# mask_v_0_0.net
KiCad netlist of a schematic drawn in Altium Designer
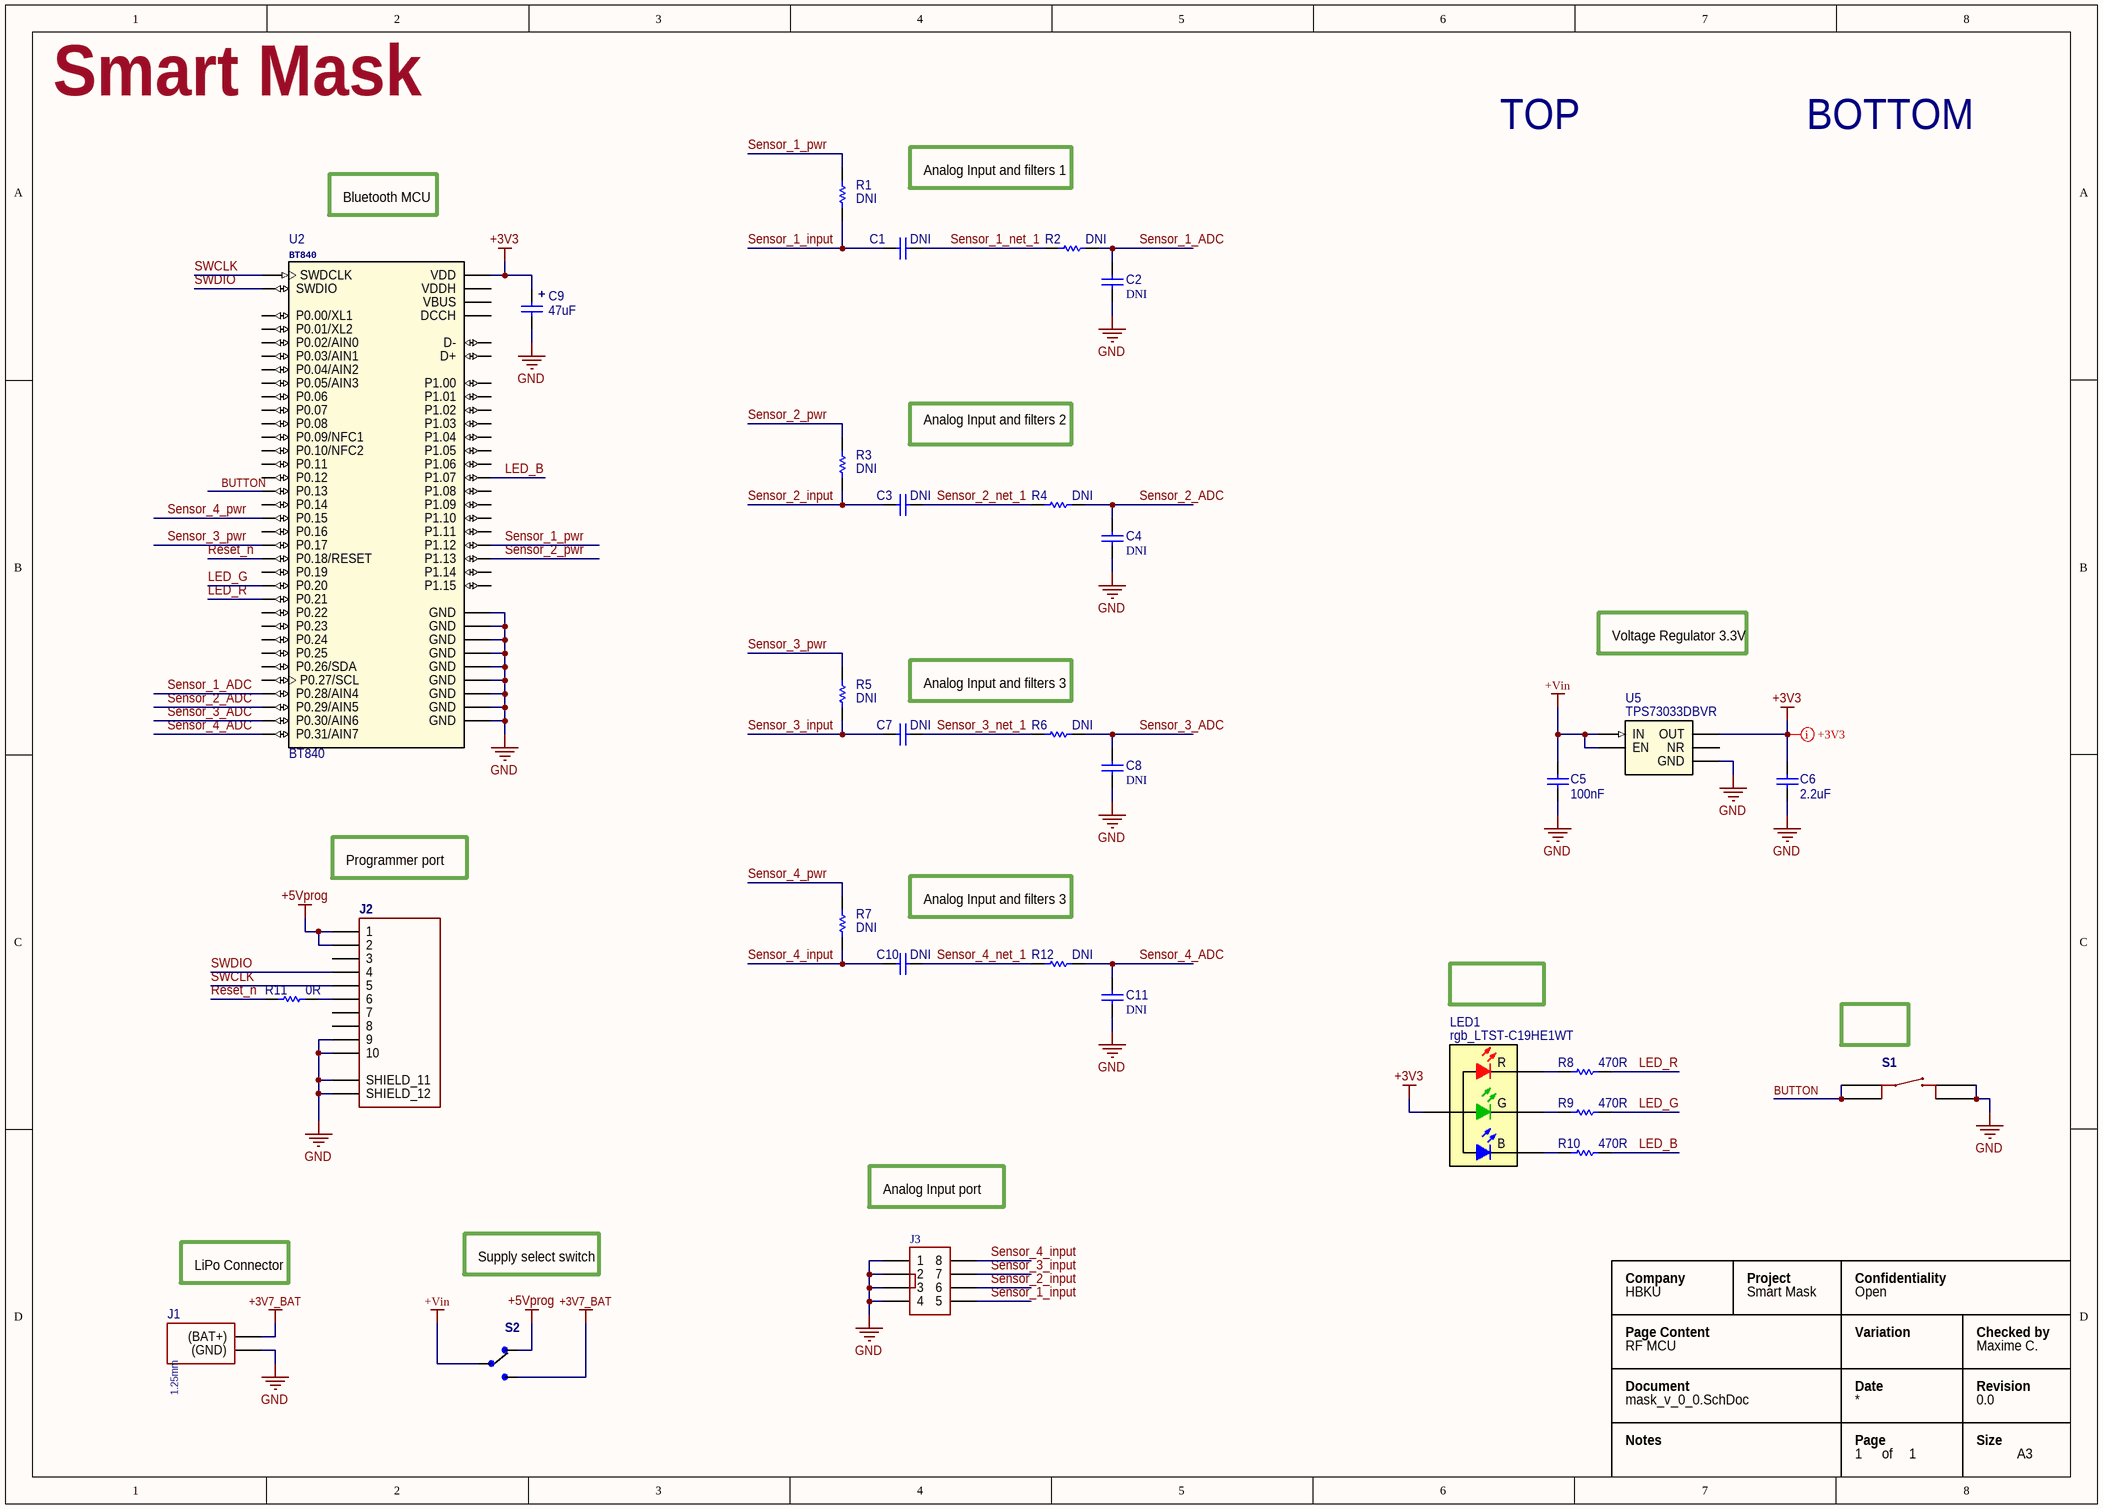
[diagram p0: mask_v_0_0.SchDoc]

(export (version "E")
  (design (tool "Eeschema 10.0.6"))
  (components
    (comp (ref "C1")
      (value "DNI")
      (footprint "C0603_DNI")
      (description "DNI (Do Not Install)")
      (fields (field (name "Comment") "Multilayer Ceramic Capacitor"))
      (libsource (lib "rcl") (part "Cap DNI 0603"))
    )
    (comp (ref "C2")
      (value "DNI")
      (footprint "C0603_DNI")
      (description "DNI (Do Not Install)")
      (fields (field (name "Comment") "Multilayer Ceramic Capacitor"))
      (libsource (lib "rcl") (part "Cap DNI 0603"))
    )
    (comp (ref "C3")
      (value "DNI")
      (footprint "C0603_DNI")
      (description "DNI (Do Not Install)")
      (fields (field (name "Comment") "Multilayer Ceramic Capacitor"))
      (libsource (lib "rcl") (part "Cap DNI 0603"))
    )
    (comp (ref "C4")
      (value "DNI")
      (footprint "C0603_DNI")
      (description "DNI (Do Not Install)")
      (fields (field (name "Comment") "Multilayer Ceramic Capacitor"))
      (libsource (lib "rcl") (part "Cap DNI 0603"))
    )
    (comp (ref "C5")
      (value "100nF")
      (footprint "C0603")
      (description "CAP CER 0.1UF 50V X7R 0603")
      (fields
        (field (name "MANUFACTURER PART NUMBER") "CL10B104KB8NNNL")
        (field (name "MANUFACTURER") "Samsung Electro-Mechanics")
      )
      (libsource (lib "rcl") (part "Cap 100nF 0603 50V"))
    )
    (comp (ref "C6")
      (value "2.2uF")
      (footprint "C0603")
      (description "CAP CER 2.2UF 10V X5R 0603")
      (fields
        (field (name "MANUFACTURER PART NUMBER") "CL10A225KP8NNNC")
        (field (name "MANUFACTURER") "Samsung Electro-Mechanics")
      )
      (libsource (lib "rcl") (part "Cap 2.2uF 0603 50V"))
    )
    (comp (ref "C7")
      (value "DNI")
      (footprint "C0603_DNI")
      (description "DNI (Do Not Install)")
      (fields (field (name "Comment") "Multilayer Ceramic Capacitor"))
      (libsource (lib "rcl") (part "Cap DNI 0603"))
    )
    (comp (ref "C8")
      (value "DNI")
      (footprint "C0603_DNI")
      (description "DNI (Do Not Install)")
      (fields (field (name "Comment") "Multilayer Ceramic Capacitor"))
      (libsource (lib "rcl") (part "Cap DNI 0603"))
    )
    (comp (ref "C9")
      (value "47uF")
      (footprint "C1206")
      (description "CAP TANT 47UF 20% 6.3V 1206")
      (fields
        (field (name "MANUFACTURER PART NUMBER") "F930J476MAA")
        (field (name "MANUFACTURER") "AVX Corporation")
      )
      (libsource (lib "rcl") (part "Cap 47uF 1206 6.3V"))
    )
    (comp (ref "C10")
      (value "DNI")
      (footprint "C0603_DNI")
      (description "DNI (Do Not Install)")
      (fields (field (name "Comment") "Multilayer Ceramic Capacitor"))
      (libsource (lib "rcl") (part "Cap DNI 0603"))
    )
    (comp (ref "C11")
      (value "DNI")
      (footprint "C0603_DNI")
      (description "DNI (Do Not Install)")
      (fields (field (name "Comment") "Multilayer Ceramic Capacitor"))
      (libsource (lib "rcl") (part "Cap DNI 0603"))
    )
    (comp (ref "J1")
      (value "BAT_0530470210")
      (footprint "Bat 1.25 mm")
      (description "CONN HEADER VERT 2POS 1.25MM")
      (fields (field (name "MANUFACTURER") "Molex") (field (name "MANUFACTURER PART NUMBER") "0530470210"))
      (libsource (lib "connectors") (part "BAT_0530470210"))
    )
    (comp (ref "J2")
      (value "FPC-10-pos")
      (footprint "FPC10")
      (description "CONN FFC TOP 10POS 0.50MM R/A \r\nFPC connector SFV10R-2STE1LF  10 positions")
      (fields
        (field (name "MANUFACTURER") "Amphenol ICC (FCI)")
        (field (name "MANUFACTURER PART NUMBER") "SFV10R-2STE1HLF")
      )
      (libsource (lib "connectors") (part "FPC-10-pos"))
    )
    (comp (ref "J3")
      (value "CON_4_2 CASE")
      (footprint "CON_4_2_CASE")
      (description "CONN HEADER VERT 8POS 2.54MM \r\nconnector 2 row 4 col (8 pos) 2.54 pitch")
      (fields (field (name "MANUFACTURER") "Molex") (field (name "MANUFACTURER PART NUMBER") "0901301208"))
      (libsource (lib "connectors") (part "CON_4_2 CASE"))
    )
    (comp (ref "LED1")
      (value "rgb_LTST-C19HE1WT")
      (footprint "LTST-C19HE1WT-4_V")
      (fields
        (field (name "MANUFACTURER") "Lite-On Inc.")
        (field (name "MANUFACTURER PART NUMBER") "LTST-C19HE1WT")
      )
      (libsource (lib "chips") (part "rgb_LTST-C19HE1WT"))
    )
    (comp (ref "R1")
      (value "DNI")
      (footprint "R0603_DNI")
      (description "DNI (Do Not Install)")
      (fields (field (name "Comment") "RES DNI 0603"))
      (libsource (lib "rcl") (part "RES DNI 0603"))
    )
    (comp (ref "R2")
      (value "DNI")
      (footprint "R0603_DNI")
      (description "DNI (Do Not Install)")
      (fields (field (name "Comment") "RES DNI 0603"))
      (libsource (lib "rcl") (part "RES DNI 0603"))
    )
    (comp (ref "R3")
      (value "DNI")
      (footprint "R0603_DNI")
      (description "DNI (Do Not Install)")
      (fields (field (name "Comment") "RES DNI 0603"))
      (libsource (lib "rcl") (part "RES DNI 0603"))
    )
    (comp (ref "R4")
      (value "DNI")
      (footprint "R0603_DNI")
      (description "DNI (Do Not Install)")
      (fields (field (name "Comment") "RES DNI 0603"))
      (libsource (lib "rcl") (part "RES DNI 0603"))
    )
    (comp (ref "R5")
      (value "DNI")
      (footprint "R0603_DNI")
      (description "DNI (Do Not Install)")
      (fields (field (name "Comment") "RES DNI 0603"))
      (libsource (lib "rcl") (part "RES DNI 0603"))
    )
    (comp (ref "R6")
      (value "DNI")
      (footprint "R0603_DNI")
      (description "DNI (Do Not Install)")
      (fields (field (name "Comment") "RES DNI 0603"))
      (libsource (lib "rcl") (part "RES DNI 0603"))
    )
    (comp (ref "R7")
      (value "DNI")
      (footprint "R0603_DNI")
      (description "DNI (Do Not Install)")
      (fields (field (name "Comment") "RES DNI 0603"))
      (libsource (lib "rcl") (part "RES DNI 0603"))
    )
    (comp (ref "R8")
      (value "470R")
      (footprint "R0603")
      (description "RES SMD 470 OHM 1% 1/10W 0603")
      (fields
        (field (name "MANUFACTURER") "Panasonic")
        (field (name "MANUFACTURER PART NUMBER") "ERJ-3EKF4700V")
      )
      (libsource (lib "rcl") (part "RES 470R 0603 1% 1/10W"))
    )
    (comp (ref "R9")
      (value "470R")
      (footprint "R0603")
      (description "RES SMD 470 OHM 1% 1/10W 0603")
      (fields
        (field (name "MANUFACTURER") "Panasonic")
        (field (name "MANUFACTURER PART NUMBER") "ERJ-3EKF4700V")
      )
      (libsource (lib "rcl") (part "RES 470R 0603 1% 1/10W"))
    )
    (comp (ref "R10")
      (value "470R")
      (footprint "R0603")
      (description "RES SMD 470 OHM 1% 1/10W 0603")
      (fields
        (field (name "MANUFACTURER") "Panasonic")
        (field (name "MANUFACTURER PART NUMBER") "ERJ-3EKF4700V")
      )
      (libsource (lib "rcl") (part "RES 470R 0603 1% 1/10W"))
    )
    (comp (ref "R11")
      (value "0R")
      (footprint "R0603")
      (description "RES SMD 0 OHM JUMPER 1/10W 0603")
      (fields
        (field (name "MANUFACTURER") "Panasonic")
        (field (name "MANUFACTURER PART NUMBER") "ERJ-3GEY0R00V")
      )
      (libsource (lib "rcl") (part "RES 0R 0603 1% 1/10W"))
    )
    (comp (ref "R12")
      (value "DNI")
      (footprint "R0603_DNI")
      (description "DNI (Do Not Install)")
      (fields (field (name "Comment") "RES DNI 0603"))
      (libsource (lib "rcl") (part "RES DNI 0603"))
    )
    (comp (ref "S1")
      (value "KMR221GLFS")
      (footprint "KMR221GLFS")
      (description "SWITCH TACTILE SPST-NO 0.05A 32V \r\nPush Button Tactile")
      (fields (field (name "MANUFACTURER") "C&K"))
      (libsource (lib "miscellaneaous") (part "KMR221GLFS"))
    )
    (comp (ref "S2")
      (value "JS102011JCQN")
      (footprint "JS102011JCQN")
      (description "SWITCH SLIDE SPDT 300MA 6V 3 ways")
      (fields (field (name "MANUFACTURER") "C&K"))
      (libsource (lib "miscellaneaous") (part "JS102011JCQN"))
    )
    (comp (ref "U2")
      (value "BT840")
      (footprint "BT840")
      (description "BLUETOOTH MODULE FANSTEL  BT840")
      (fields (field (name "MANUFACTURER") "Fanstel") (field (name "MANUFACTURER PART NUMBER") "BT840"))
      (libsource (lib "chips") (part "BT840"))
    )
    (comp (ref "U5")
      (value "TPS73033DBVR")
      (footprint "TPS73033DBV")
      (description "IC REG LINEAR 3.3V 200MA SOT23-5")
      (fields
        (field (name "MANUFACTURER") "Texas Instruments")
        (field (name "MANUFACTURER PART NUMBER") "TPS73033DBVR")
      )
      (libsource (lib "chips") (part "TPS73033DBVR"))
    )
  )
  (nets
    (net (code "1") (name "+3V3") (class "Default")
      (node (ref "C6") (pin "2") (pinfunction "2_2") (pintype "passive"))
      (node (ref "C9") (pin "1") (pinfunction "1_1") (pintype "passive"))
      (node (ref "LED1") (pin "4") (pinfunction "A_4") (pintype "passive"))
      (node (ref "U2") (pin "9") (pinfunction "VDD_9") (pintype "power_in"))
      (node (ref "U5") (pin "5") (pinfunction "OUT_5") (pintype "power_in"))
    )
    (net (code "2") (name "+3V7_BAT") (class "Default")
      (node (ref "J1") (pin "1") (pinfunction "(BAT+)_1") (pintype "passive"))
      (node (ref "S2") (pin "3") (pinfunction "3_3") (pintype "passive"))
    )
    (net (code "3") (name "+5Vprog") (class "Default")
      (node (ref "J2") (pin "1") (pinfunction "1_1") (pintype "passive"))
      (node (ref "J2") (pin "2") (pinfunction "2_2") (pintype "passive"))
      (node (ref "S2") (pin "1") (pinfunction "1_1") (pintype "passive"))
    )
    (net (code "4") (name "+Vin") (class "Default")
      (node (ref "C5") (pin "2") (pinfunction "2_2") (pintype "passive"))
      (node (ref "S2") (pin "2") (pinfunction "2_2") (pintype "passive"))
      (node (ref "U5") (pin "1") (pinfunction "IN_1") (pintype "input"))
      (node (ref "U5") (pin "3") (pinfunction "EN_3") (pintype "passive"))
    )
    (net (code "5") (name "/BUTTON") (class "Default")
      (node (ref "S1") (pin "1") (pinfunction "1_1") (pintype "passive"))
      (node (ref "S1") (pin "4") (pinfunction "4_4") (pintype "passive"))
      (node (ref "U2") (pin "13") (pinfunction "P0.13_13") (pintype "bidirectional"))
    )
    (net (code "6") (name "/LED_B") (class "Default")
      (node (ref "R10") (pin "2") (pinfunction "2_2") (pintype "passive"))
      (node (ref "U2") (pin "E0") (pinfunction "P1.07_E0") (pintype "bidirectional"))
    )
    (net (code "7") (name "/LED_G") (class "Default")
      (node (ref "R9") (pin "2") (pinfunction "2_2") (pintype "passive"))
      (node (ref "U2") (pin "E1") (pinfunction "P0.20_E1") (pintype "bidirectional"))
    )
    (net (code "8") (name "/LED_R") (class "Default")
      (node (ref "R8") (pin "2") (pinfunction "2_2") (pintype "passive"))
      (node (ref "U2") (pin "E2") (pinfunction "P0.21_E2") (pintype "bidirectional"))
    )
    (net (code "9") (name "/Reset_n") (class "Default")
      (node (ref "R11") (pin "1") (pinfunction "1_1") (pintype "passive"))
      (node (ref "U2") (pin "14") (pinfunction "P0.18/RESET_14") (pintype "bidirectional"))
    )
    (net (code "10") (name "/SWCLK") (class "Default")
      (node (ref "J2") (pin "5") (pinfunction "5_5") (pintype "passive"))
      (node (ref "U2") (pin "15") (pinfunction "SWDCLK_15") (pintype "input"))
    )
    (net (code "11") (name "/SWDIO") (class "Default")
      (node (ref "J2") (pin "4") (pinfunction "4_4") (pintype "passive"))
      (node (ref "U2") (pin "16") (pinfunction "SWDIO_16") (pintype "bidirectional"))
    )
    (net (code "12") (name "/Sensor_1_ADC") (class "Default")
      (node (ref "C2") (pin "2") (pinfunction "2_2") (pintype "passive"))
      (node (ref "R2") (pin "2") (pinfunction "2_2") (pintype "passive"))
      (node (ref "U2") (pin "A1") (pinfunction "P0.28/AIN4_A1") (pintype "bidirectional"))
    )
    (net (code "13") (name "/Sensor_1_input") (class "Default")
      (node (ref "C1") (pin "1") (pinfunction "1_1") (pintype "passive"))
      (node (ref "J3") (pin "5") (pinfunction "5_5") (pintype "passive"))
      (node (ref "R1") (pin "1") (pinfunction "1_1") (pintype "passive"))
    )
    (net (code "14") (name "/Sensor_1_net_1") (class "Default")
      (node (ref "C1") (pin "2") (pinfunction "2_2") (pintype "passive"))
      (node (ref "R2") (pin "1") (pinfunction "1_1") (pintype "passive"))
    )
    (net (code "15") (name "/Sensor_1_pwr") (class "Default")
      (node (ref "R1") (pin "2") (pinfunction "2_2") (pintype "passive"))
      (node (ref "U2") (pin "Z1") (pinfunction "P1.12_Z1") (pintype "bidirectional"))
    )
    (net (code "16") (name "/Sensor_2_ADC") (class "Default")
      (node (ref "C4") (pin "2") (pinfunction "2_2") (pintype "passive"))
      (node (ref "R4") (pin "2") (pinfunction "2_2") (pintype "passive"))
      (node (ref "U2") (pin "A2") (pinfunction "P0.29/AIN5_A2") (pintype "bidirectional"))
    )
    (net (code "17") (name "/Sensor_2_input") (class "Default")
      (node (ref "C3") (pin "1") (pinfunction "1_1") (pintype "passive"))
      (node (ref "J3") (pin "6") (pinfunction "6_6") (pintype "passive"))
      (node (ref "R3") (pin "1") (pinfunction "1_1") (pintype "passive"))
    )
    (net (code "18") (name "/Sensor_2_net_1") (class "Default")
      (node (ref "C3") (pin "2") (pinfunction "2_2") (pintype "passive"))
      (node (ref "R4") (pin "1") (pinfunction "1_1") (pintype "passive"))
    )
    (net (code "19") (name "/Sensor_2_pwr") (class "Default")
      (node (ref "R3") (pin "2") (pinfunction "2_2") (pintype "passive"))
      (node (ref "U2") (pin "Z2") (pinfunction "P1.13_Z2") (pintype "bidirectional"))
    )
    (net (code "20") (name "/Sensor_3_ADC") (class "Default")
      (node (ref "C8") (pin "2") (pinfunction "2_2") (pintype "passive"))
      (node (ref "R6") (pin "2") (pinfunction "2_2") (pintype "passive"))
      (node (ref "U2") (pin "B2") (pinfunction "P0.30/AIN6_B2") (pintype "bidirectional"))
    )
    (net (code "21") (name "/Sensor_3_input") (class "Default")
      (node (ref "C7") (pin "1") (pinfunction "1_1") (pintype "passive"))
      (node (ref "J3") (pin "7") (pinfunction "7_7") (pintype "passive"))
      (node (ref "R5") (pin "1") (pinfunction "1_1") (pintype "passive"))
    )
    (net (code "22") (name "/Sensor_3_net_1") (class "Default")
      (node (ref "C7") (pin "2") (pinfunction "2_2") (pintype "passive"))
      (node (ref "R6") (pin "1") (pinfunction "1_1") (pintype "passive"))
    )
    (net (code "23") (name "/Sensor_3_pwr") (class "Default")
      (node (ref "R5") (pin "2") (pinfunction "2_2") (pintype "passive"))
      (node (ref "U2") (pin "C3") (pinfunction "P0.17_C3") (pintype "bidirectional"))
    )
    (net (code "24") (name "/Sensor_4_ADC") (class "Default")
      (node (ref "C11") (pin "2") (pinfunction "2_2") (pintype "passive"))
      (node (ref "R12") (pin "2") (pinfunction "2_2") (pintype "passive"))
      (node (ref "U2") (pin "B3") (pinfunction "P0.31/AIN7_B3") (pintype "bidirectional"))
    )
    (net (code "25") (name "/Sensor_4_input") (class "Default")
      (node (ref "C10") (pin "1") (pinfunction "1_1") (pintype "passive"))
      (node (ref "J3") (pin "8") (pinfunction "8_8") (pintype "passive"))
      (node (ref "R7") (pin "1") (pinfunction "1_1") (pintype "passive"))
    )
    (net (code "26") (name "/Sensor_4_net_1") (class "Default")
      (node (ref "C10") (pin "2") (pinfunction "2_2") (pintype "passive"))
      (node (ref "R12") (pin "1") (pinfunction "1_1") (pintype "passive"))
    )
    (net (code "27") (name "/Sensor_4_pwr") (class "Default")
      (node (ref "R7") (pin "2") (pinfunction "2_2") (pintype "passive"))
      (node (ref "U2") (pin "C4") (pinfunction "P0.15_C4") (pintype "bidirectional"))
    )
    (net (code "28") (name "GND") (class "Default")
      (node (ref "C11") (pin "1") (pinfunction "1_1") (pintype "passive"))
      (node (ref "C2") (pin "1") (pinfunction "1_1") (pintype "passive"))
      (node (ref "C4") (pin "1") (pinfunction "1_1") (pintype "passive"))
      (node (ref "C5") (pin "1") (pinfunction "1_1") (pintype "passive"))
      (node (ref "C6") (pin "1") (pinfunction "1_1") (pintype "passive"))
      (node (ref "C8") (pin "1") (pinfunction "1_1") (pintype "passive"))
      (node (ref "C9") (pin "2") (pinfunction "2_2") (pintype "passive"))
      (node (ref "J1") (pin "2") (pinfunction "(GND)_2") (pintype "passive"))
      (node (ref "J2") (pin "10") (pinfunction "10_10") (pintype "passive"))
      (node (ref "J2") (pin "11") (pinfunction "SHIELD_11_11") (pintype "passive"))
      (node (ref "J2") (pin "12") (pinfunction "SHIELD_12_12") (pintype "passive"))
      (node (ref "J2") (pin "9") (pinfunction "9_9") (pintype "passive"))
      (node (ref "J3") (pin "1") (pinfunction "1_1") (pintype "passive"))
      (node (ref "J3") (pin "2") (pinfunction "2_2") (pintype "passive"))
      (node (ref "J3") (pin "3") (pinfunction "3_3") (pintype "passive"))
      (node (ref "J3") (pin "4") (pinfunction "4_4") (pintype "passive"))
      (node (ref "S1") (pin "2") (pinfunction "2_2") (pintype "passive"))
      (node (ref "S1") (pin "3") (pinfunction "3_3") (pintype "passive"))
      (node (ref "U2") (pin "10") (pinfunction "GND_10") (pintype "power_in"))
      (node (ref "U2") (pin "A0") (pinfunction "GND_A0") (pintype "power_in"))
      (node (ref "U2") (pin "B0") (pinfunction "GND_B0") (pintype "power_in"))
      (node (ref "U2") (pin "C0") (pinfunction "GND_C0") (pintype "power_in"))
      (node (ref "U2") (pin "D0") (pinfunction "GND_D0") (pintype "power_in"))
      (node (ref "U2") (pin "F0") (pinfunction "GND_F0") (pintype "power_in"))
      (node (ref "U2") (pin "F1") (pinfunction "GND_F1") (pintype "power_in"))
      (node (ref "U2") (pin "F2") (pinfunction "GND_F2") (pintype "power_in"))
      (node (ref "U2") (pin "F3") (pinfunction "GND_F3") (pintype "power_in"))
      (node (ref "U5") (pin "2") (pinfunction "GND_2") (pintype "power_in"))
    )
    (net (code "29") (name "Net-(J2-Pad6)") (class "Default")
      (node (ref "J2") (pin "6") (pinfunction "6_6") (pintype "passive"))
      (node (ref "R11") (pin "2") (pinfunction "2_2") (pintype "passive"))
    )
    (net (code "30") (name "Net-(LED1-B)") (class "Default")
      (node (ref "LED1") (pin "3") (pinfunction "B_3") (pintype "passive"))
      (node (ref "R10") (pin "1") (pinfunction "1_1") (pintype "passive"))
    )
    (net (code "31") (name "Net-(LED1-G)") (class "Default")
      (node (ref "LED1") (pin "2") (pinfunction "G_2") (pintype "passive"))
      (node (ref "R9") (pin "1") (pinfunction "1_1") (pintype "passive"))
    )
    (net (code "32") (name "Net-(LED1-R)") (class "Default")
      (node (ref "LED1") (pin "1") (pinfunction "R_1") (pintype "passive"))
      (node (ref "R8") (pin "1") (pinfunction "1_1") (pintype "passive"))
    )
    (net (code "33") (name "unconnected-(J2-Pad3)") (class "Default")
      (node (ref "J2") (pin "3") (pinfunction "3_3") (pintype "passive"))
    )
    (net (code "34") (name "unconnected-(J2-Pad7)") (class "Default")
      (node (ref "J2") (pin "7") (pinfunction "7_7") (pintype "passive"))
    )
    (net (code "35") (name "unconnected-(J2-Pad8)") (class "Default")
      (node (ref "J2") (pin "8") (pinfunction "8_8") (pintype "passive"))
    )
    (net (code "36") (name "unconnected-(U2-D+-PadE4)") (class "Default")
      (node (ref "U2") (pin "E4") (pinfunction "D+_E4") (pintype "bidirectional"))
    )
    (net (code "37") (name "unconnected-(U2-D--PadE5)") (class "Default")
      (node (ref "U2") (pin "E5") (pinfunction "D-_E5") (pintype "bidirectional"))
    )
    (net (code "38") (name "unconnected-(U2-DCCH-PadF5)") (class "Default")
      (node (ref "U2") (pin "F5") (pinfunction "DCCH_F5") (pintype "power_in"))
    )
    (net (code "39") (name "unconnected-(U2-P0.00{slash}XL1-Pad3)") (class "Default")
      (node (ref "U2") (pin "3") (pinfunction "P0.00/XL1_3") (pintype "bidirectional"))
    )
    (net (code "40") (name "unconnected-(U2-P0.01{slash}XL2-Pad4)") (class "Default")
      (node (ref "U2") (pin "4") (pinfunction "P0.01/XL2_4") (pintype "bidirectional"))
    )
    (net (code "41") (name "unconnected-(U2-P0.02{slash}AIN0-Pad5)") (class "Default")
      (node (ref "U2") (pin "5") (pinfunction "P0.02/AIN0_5") (pintype "bidirectional"))
    )
    (net (code "42") (name "unconnected-(U2-P0.03{slash}AIN1-Pad6)") (class "Default")
      (node (ref "U2") (pin "6") (pinfunction "P0.03/AIN1_6") (pintype "bidirectional"))
    )
    (net (code "43") (name "unconnected-(U2-P0.04{slash}AIN2-PadA3)") (class "Default")
      (node (ref "U2") (pin "A3") (pinfunction "P0.04/AIN2_A3") (pintype "bidirectional"))
    )
    (net (code "44") (name "unconnected-(U2-P0.05{slash}AIN3-PadA4)") (class "Default")
      (node (ref "U2") (pin "A4") (pinfunction "P0.05/AIN3_A4") (pintype "bidirectional"))
    )
    (net (code "45") (name "unconnected-(U2-P0.06-PadB4)") (class "Default")
      (node (ref "U2") (pin "B4") (pinfunction "P0.06_B4") (pintype "bidirectional"))
    )
    (net (code "46") (name "unconnected-(U2-P0.07-PadA5)") (class "Default")
      (node (ref "U2") (pin "A5") (pinfunction "P0.07_A5") (pintype "bidirectional"))
    )
    (net (code "47") (name "unconnected-(U2-P0.08-PadB5)") (class "Default")
      (node (ref "U2") (pin "B5") (pinfunction "P0.08_B5") (pintype "bidirectional"))
    )
    (net (code "48") (name "unconnected-(U2-P0.09{slash}NFC1-Pad7)") (class "Default")
      (node (ref "U2") (pin "7") (pinfunction "P0.09/NFC1_7") (pintype "bidirectional"))
    )
    (net (code "49") (name "unconnected-(U2-P0.10{slash}NFC2-Pad8)") (class "Default")
      (node (ref "U2") (pin "8") (pinfunction "P0.10/NFC2_8") (pintype "bidirectional"))
    )
    (net (code "50") (name "unconnected-(U2-P0.11-Pad11)") (class "Default")
      (node (ref "U2") (pin "11") (pinfunction "P0.11_11") (pintype "bidirectional"))
    )
    (net (code "51") (name "unconnected-(U2-P0.12-PadE6)") (class "Default")
      (node (ref "U2") (pin "E6") (pinfunction "P0.12_E6") (pintype "bidirectional"))
    )
    (net (code "52") (name "unconnected-(U2-P0.14-PadD4)") (class "Default")
      (node (ref "U2") (pin "D4") (pinfunction "P0.14_D4") (pintype "bidirectional"))
    )
    (net (code "53") (name "unconnected-(U2-P0.16-PadD3)") (class "Default")
      (node (ref "U2") (pin "D3") (pinfunction "P0.16_D3") (pintype "bidirectional"))
    )
    (net (code "54") (name "unconnected-(U2-P0.19-PadD2)") (class "Default")
      (node (ref "U2") (pin "D2") (pinfunction "P0.19_D2") (pintype "bidirectional"))
    )
    (net (code "55") (name "unconnected-(U2-P0.22-PadC2)") (class "Default")
      (node (ref "U2") (pin "C2") (pinfunction "P0.22_C2") (pintype "bidirectional"))
    )
    (net (code "56") (name "unconnected-(U2-P0.23-PadD1)") (class "Default")
      (node (ref "U2") (pin "D1") (pinfunction "P0.23_D1") (pintype "bidirectional"))
    )
    (net (code "57") (name "unconnected-(U2-P0.24-PadC1)") (class "Default")
      (node (ref "U2") (pin "C1") (pinfunction "P0.24_C1") (pintype "bidirectional"))
    )
    (net (code "58") (name "unconnected-(U2-P0.25-PadB1)") (class "Default")
      (node (ref "U2") (pin "B1") (pinfunction "P0.25_B1") (pintype "bidirectional"))
    )
    (net (code "59") (name "unconnected-(U2-P0.26{slash}SDA-Pad1)") (class "Default")
      (node (ref "U2") (pin "1") (pinfunction "P0.26/SDA_1") (pintype "bidirectional"))
    )
    (net (code "60") (name "unconnected-(U2-P0.27{slash}SCL-Pad2)") (class "Default")
      (node (ref "U2") (pin "2") (pinfunction "P0.27/SCL_2") (pintype "bidirectional"))
    )
    (net (code "61") (name "unconnected-(U2-P1.00-Pad12)") (class "Default")
      (node (ref "U2") (pin "12") (pinfunction "P1.00_12") (pintype "bidirectional"))
    )
    (net (code "62") (name "unconnected-(U2-P1.01-PadD5)") (class "Default")
      (node (ref "U2") (pin "D5") (pinfunction "P1.01_D5") (pintype "bidirectional"))
    )
    (net (code "63") (name "unconnected-(U2-P1.02-PadC5)") (class "Default")
      (node (ref "U2") (pin "C5") (pinfunction "P1.02_C5") (pintype "bidirectional"))
    )
    (net (code "64") (name "unconnected-(U2-P1.03-PadB6)") (class "Default")
      (node (ref "U2") (pin "B6") (pinfunction "P1.03_B6") (pintype "bidirectional"))
    )
    (net (code "65") (name "unconnected-(U2-P1.04-PadC6)") (class "Default")
      (node (ref "U2") (pin "C6") (pinfunction "P1.04_C6") (pintype "bidirectional"))
    )
    (net (code "66") (name "unconnected-(U2-P1.05-PadD6)") (class "Default")
      (node (ref "U2") (pin "D6") (pinfunction "P1.05_D6") (pintype "bidirectional"))
    )
    (net (code "67") (name "unconnected-(U2-P1.06-PadZ6)") (class "Default")
      (node (ref "U2") (pin "Z6") (pinfunction "P1.06_Z6") (pintype "bidirectional"))
    )
    (net (code "68") (name "unconnected-(U2-P1.08-PadA6)") (class "Default")
      (node (ref "U2") (pin "A6") (pinfunction "P1.08_A6") (pintype "bidirectional"))
    )
    (net (code "69") (name "unconnected-(U2-P1.09-PadE3)") (class "Default")
      (node (ref "U2") (pin "E3") (pinfunction "P1.09_E3") (pintype "bidirectional"))
    )
    (net (code "70") (name "unconnected-(U2-P1.10-PadZ5)") (class "Default")
      (node (ref "U2") (pin "Z5") (pinfunction "P1.10_Z5") (pintype "bidirectional"))
    )
    (net (code "71") (name "unconnected-(U2-P1.11-PadZ0)") (class "Default")
      (node (ref "U2") (pin "Z0") (pinfunction "P1.11_Z0") (pintype "bidirectional"))
    )
    (net (code "72") (name "unconnected-(U2-P1.14-PadZ3)") (class "Default")
      (node (ref "U2") (pin "Z3") (pinfunction "P1.14_Z3") (pintype "bidirectional"))
    )
    (net (code "73") (name "unconnected-(U2-P1.15-PadZ4)") (class "Default")
      (node (ref "U2") (pin "Z4") (pinfunction "P1.15_Z4") (pintype "bidirectional"))
    )
    (net (code "74") (name "unconnected-(U2-VBUS-PadF6)") (class "Default")
      (node (ref "U2") (pin "F6") (pinfunction "VBUS_F6") (pintype "power_in"))
    )
    (net (code "75") (name "unconnected-(U2-VDDH-PadF4)") (class "Default")
      (node (ref "U2") (pin "F4") (pinfunction "VDDH_F4") (pintype "power_in"))
    )
    (net (code "76") (name "unconnected-(U5-NR-Pad4)") (class "Default")
      (node (ref "U5") (pin "4") (pinfunction "NR_4") (pintype "passive"))
    )
  )
)
